# SCH_Motor_PCB_2026-05-03.net
KiCad netlist of a schematic drawn in EasyEDA
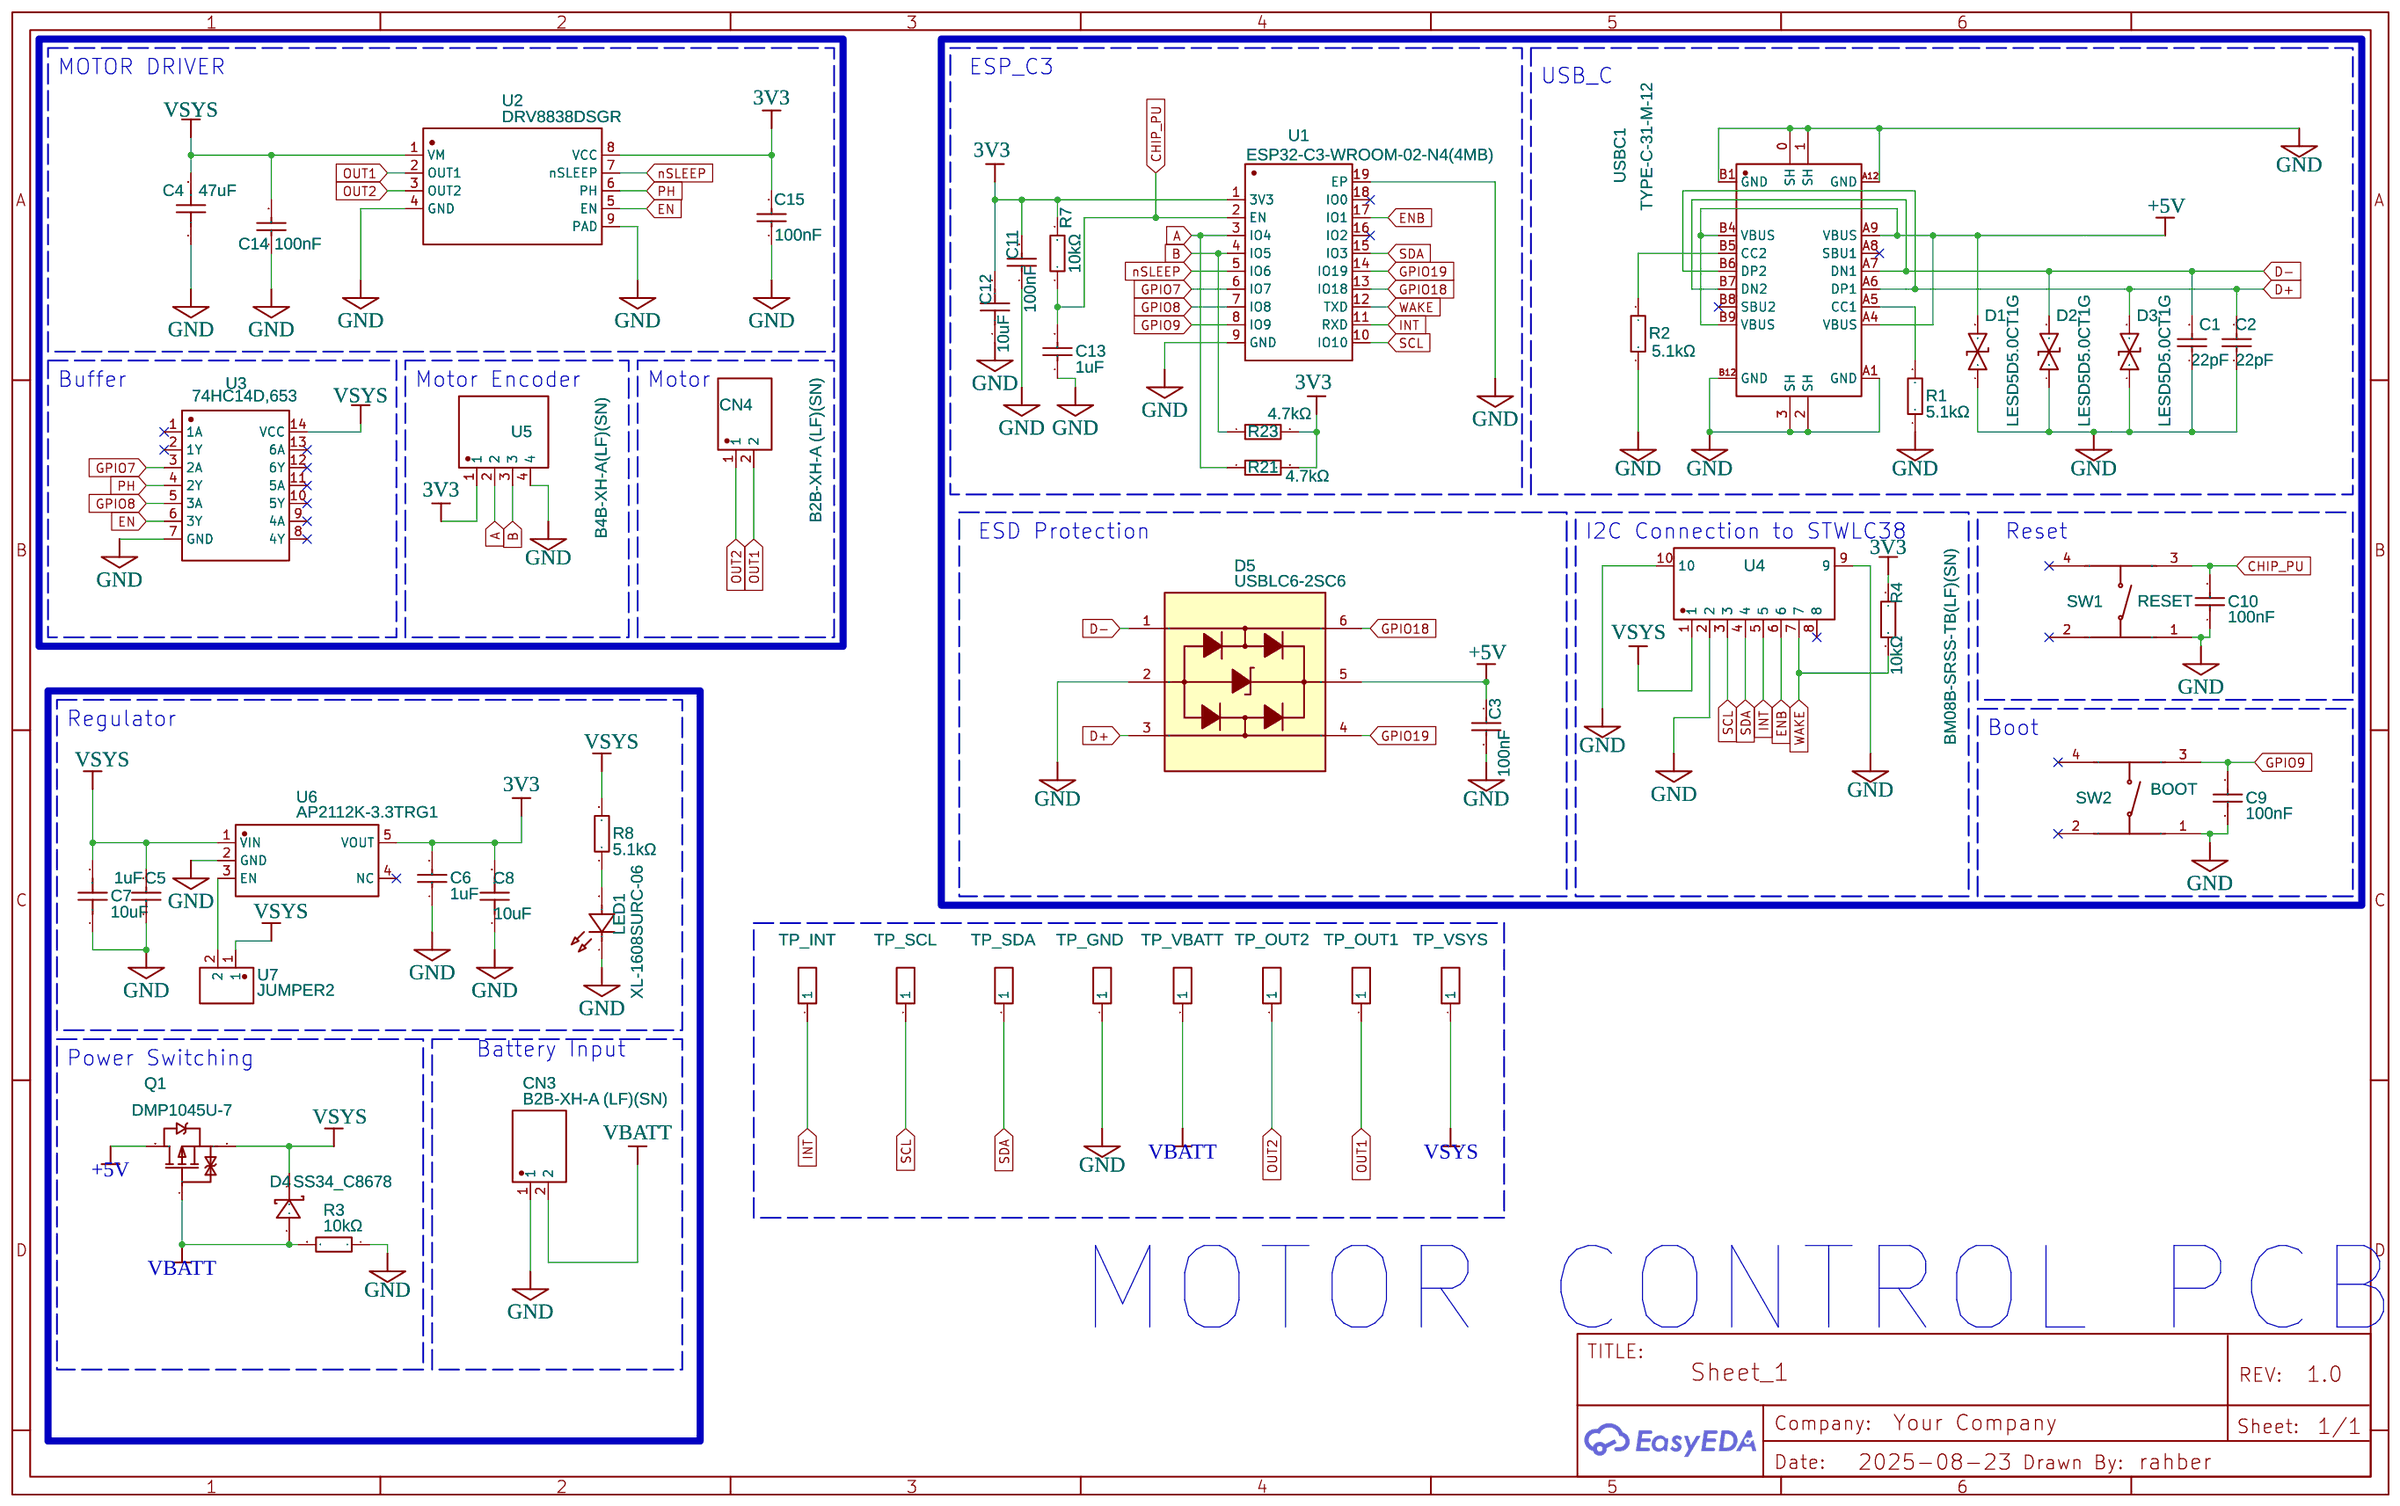
[diagram p0: schematic sheet]

(export (version "E")
  (design (tool "Eeschema 10.0.6"))
  (components
    (comp (ref "BOOT")
      (value "SW2")
      (fields
        (field (name "Manufacturer Part") "TS-1157-C-E")
        (field (name "Manufacturer") "XKB Connectivity(中国星坤)")
      )
      (libsource (lib "") (part "TS-1157-C-E_1"))
    )
    (comp (ref "C1")
      (value "22pF")
      (fields
        (field (name "Manufacturer Part") "CL10C220JB8NNNC")
        (field (name "Manufacturer") "SAMSUNG(三星)")
      )
      (libsource (lib "") (part "CL10C220JB8NNNC"))
    )
    (comp (ref "C2")
      (value "22pF")
      (fields
        (field (name "Manufacturer Part") "CL10C220JB8NNNC")
        (field (name "Manufacturer") "SAMSUNG(三星)")
      )
      (libsource (lib "") (part "CL10C220JB8NNNC"))
    )
    (comp (ref "C3")
      (value "100nF")
      (fields
        (field (name "Manufacturer Part") "CT41G-0603-2X1-50V-0.1μF-K(N)")
        (field (name "Manufacturer") "TORCH(火炬)")
      )
      (libsource (lib "") (part "CT41G-0603-2X1-50V-0.1μF-K(N)"))
    )
    (comp (ref "C4")
      (value "47uF")
      (fields
        (field (name "Manufacturer Part") "CGA0805X5R476M100MT")
        (field (name "Manufacturer") "HRE(芯声)")
      )
      (libsource (lib "") (part "CGA0805X5R476M100MT"))
    )
    (comp (ref "C5")
      (value "1uF")
      (fields
        (field (name "Manufacturer Part") "CL10A105KO8NNNC")
        (field (name "Manufacturer") "SAMSUNG(三星)")
      )
      (libsource (lib "") (part "CL10A105KO8NNNC"))
    )
    (comp (ref "C6")
      (value "1uF")
      (fields
        (field (name "Manufacturer Part") "CL10A105KO8NNNC")
        (field (name "Manufacturer") "SAMSUNG(三星)")
      )
      (libsource (lib "") (part "CL10A105KO8NNNC"))
    )
    (comp (ref "C7")
      (value "10uF")
      (fields
        (field (name "Manufacturer Part") "CL10A106MA8NRNC")
        (field (name "Manufacturer") "SAMSUNG(三星)")
      )
      (libsource (lib "") (part "CL10A106MA8NRNC"))
    )
    (comp (ref "C8")
      (value "10uF")
      (fields
        (field (name "Manufacturer Part") "CL10A106MA8NRNC")
        (field (name "Manufacturer") "SAMSUNG(三星)")
      )
      (libsource (lib "") (part "CL10A106MA8NRNC"))
    )
    (comp (ref "C9")
      (value "100nF")
      (fields
        (field (name "Manufacturer Part") "CT41G-0603-2X1-50V-0.1μF-K(N)")
        (field (name "Manufacturer") "TORCH(火炬)")
      )
      (libsource (lib "") (part "CT41G-0603-2X1-50V-0.1μF-K(N)"))
    )
    (comp (ref "C10")
      (value "100nF")
      (fields
        (field (name "Manufacturer Part") "CT41G-0603-2X1-50V-0.1μF-K(N)")
        (field (name "Manufacturer") "TORCH(火炬)")
      )
      (libsource (lib "") (part "CT41G-0603-2X1-50V-0.1μF-K(N)"))
    )
    (comp (ref "C11")
      (value "100nF")
      (fields
        (field (name "Manufacturer Part") "CT41G-0603-2X1-50V-0.1μF-K(N)")
        (field (name "Manufacturer") "TORCH(火炬)")
      )
      (libsource (lib "") (part "CT41G-0603-2X1-50V-0.1μF-K(N)"))
    )
    (comp (ref "C12")
      (value "10uF")
      (fields
        (field (name "Manufacturer Part") "CL10A106MA8NRNC")
        (field (name "Manufacturer") "SAMSUNG(三星)")
      )
      (libsource (lib "") (part "CL10A106MA8NRNC"))
    )
    (comp (ref "C13")
      (value "1uF")
      (fields
        (field (name "Manufacturer Part") "CL10A105KO8NNNC")
        (field (name "Manufacturer") "SAMSUNG(三星)")
      )
      (libsource (lib "") (part "CL10A105KO8NNNC"))
    )
    (comp (ref "C14")
      (value "100nF")
      (fields
        (field (name "Manufacturer Part") "CT41G-0603-2X1-50V-0.1μF-K(N)")
        (field (name "Manufacturer") "TORCH(火炬)")
      )
      (libsource (lib "") (part "CT41G-0603-2X1-50V-0.1μF-K(N)"))
    )
    (comp (ref "C15")
      (value "100nF")
      (fields
        (field (name "Manufacturer Part") "CT41G-0603-2X1-50V-0.1μF-K(N)")
        (field (name "Manufacturer") "TORCH(火炬)")
      )
      (libsource (lib "") (part "CT41G-0603-2X1-50V-0.1μF-K(N)"))
    )
    (comp (ref "CN3")
      (value "B2B-XH-A (LF)(SN)")
      (fields (field (name "Manufacturer Part") "B2B-XH-A(LF)(SN)") (field (name "Manufacturer") "JST"))
      (libsource (lib "") (part "B2B-XH-A (LF)(SN)"))
    )
    (comp (ref "CN4")
      (value "B2B-XH-A (LF)(SN)")
      (fields (field (name "Manufacturer Part") "B2B-XH-A(LF)(SN)") (field (name "Manufacturer") "JST"))
      (libsource (lib "") (part "B2B-XH-A (LF)(SN)"))
    )
    (comp (ref "D1")
      (value "LESD5D5.0CT1G")
      (fields (field (name "Manufacturer") "LRC(乐山无线电)"))
      (libsource (lib "") (part "LESD5D5.0CT1G"))
    )
    (comp (ref "D2")
      (value "LESD5D5.0CT1G")
      (fields (field (name "Manufacturer") "LRC(乐山无线电)"))
      (libsource (lib "") (part "LESD5D5.0CT1G"))
    )
    (comp (ref "D3")
      (value "LESD5D5.0CT1G")
      (fields (field (name "Manufacturer") "LRC(乐山无线电)"))
      (libsource (lib "") (part "LESD5D5.0CT1G"))
    )
    (comp (ref "D4")
      (value "SS34_C8678")
      (fields (field (name "Manufacturer Part") "SS34") (field (name "Manufacturer") "MDD(辰达半导体)"))
      (libsource (lib "") (part "SS34_C8678"))
    )
    (comp (ref "D5")
      (value "USBLC6-2SC6")
      (fields (field (name "Manufacturer") "ST(意法半导体)"))
      (libsource (lib "") (part "USBLC6-2SC6"))
    )
    (comp (ref "LED1")
      (value "XL-1608SURC-06")
      (fields (field (name "Manufacturer") "XINGLIGHT(成兴光)"))
      (libsource (lib "") (part "XL-1608SURC-06"))
    )
    (comp (ref "Q1")
      (value "DMP1045U-7")
      (fields (field (name "Manufacturer") "DIODES(美台)"))
      (libsource (lib "") (part "DMP1045U-7"))
    )
    (comp (ref "R1")
      (value "5.1kΩ")
      (fields (field (name "Manufacturer Part") "RC0603FR-075K1L") (field (name "Manufacturer") "YAGEO(国巨)"))
      (libsource (lib "") (part "RC0603FR-075K1L"))
    )
    (comp (ref "R2")
      (value "5.1kΩ")
      (fields (field (name "Manufacturer Part") "RC0603FR-075K1L") (field (name "Manufacturer") "YAGEO(国巨)"))
      (libsource (lib "") (part "RC0603FR-075K1L"))
    )
    (comp (ref "R3")
      (value "10kΩ")
      (fields (field (name "Manufacturer Part") "RC0603FR-0710KL") (field (name "Manufacturer") "YAGEO(国巨)"))
      (libsource (lib "") (part "RC0603FR-0710KL"))
    )
    (comp (ref "R4")
      (value "10kΩ")
      (fields (field (name "Manufacturer Part") "RC0603FR-0710KL") (field (name "Manufacturer") "YAGEO(国巨)"))
      (libsource (lib "") (part "RC0603FR-0710KL_2"))
    )
    (comp (ref "R7")
      (value "10kΩ")
      (fields (field (name "Manufacturer Part") "RC0603FR-0710KL") (field (name "Manufacturer") "YAGEO(国巨)"))
      (libsource (lib "") (part "RC0603FR-0710KL_1"))
    )
    (comp (ref "R8")
      (value "5.1kΩ")
      (fields (field (name "Manufacturer Part") "RC0603FR-075K1L") (field (name "Manufacturer") "YAGEO(国巨)"))
      (libsource (lib "") (part "RC0603FR-075K1L"))
    )
    (comp (ref "R21")
      (value "4.7kΩ")
      (fields
        (field (name "Manufacturer Part") "0805W8F4701T5E")
        (field (name "Manufacturer") "UNI-ROYAL(厚声)")
      )
      (libsource (lib "") (part "0805W8F4701T5E"))
    )
    (comp (ref "R23")
      (value "4.7kΩ")
      (fields
        (field (name "Manufacturer Part") "0805W8F4701T5E")
        (field (name "Manufacturer") "UNI-ROYAL(厚声)")
      )
      (libsource (lib "") (part "0805W8F4701T5E"))
    )
    (comp (ref "RESET")
      (value "SW1")
      (fields
        (field (name "Manufacturer Part") "TS-1157-C-E")
        (field (name "Manufacturer") "XKB Connectivity(中国星坤)")
      )
      (libsource (lib "") (part "TS-1157-C-E"))
    )
    (comp (ref "TP_GND") (value "HDR-M-2.54_1x1") (libsource (lib "") (part "HDR-M-2.54_1x1_4")))
    (comp (ref "TP_INT") (value "HDR-M-2.54_1x1") (libsource (lib "") (part "HDR-M-2.54_1x1_5")))
    (comp (ref "TP_OUT1") (value "HDR-M-2.54_1x1") (libsource (lib "") (part "HDR-M-2.54_1x1_3")))
    (comp (ref "TP_OUT2") (value "HDR-M-2.54_1x1") (libsource (lib "") (part "HDR-M-2.54_1x1_3")))
    (comp (ref "TP_SCL") (value "HDR-M-2.54_1x1") (libsource (lib "") (part "HDR-M-2.54_1x1")))
    (comp (ref "TP_SDA") (value "HDR-M-2.54_1x1") (libsource (lib "") (part "HDR-M-2.54_1x1_2")))
    (comp (ref "TP_VBATT") (value "HDR-M-2.54_1x1") (libsource (lib "") (part "HDR-M-2.54_1x1_6")))
    (comp (ref "TP_VSYS") (value "HDR-M-2.54_1x1") (libsource (lib "") (part "HDR-M-2.54_1x1_1")))
    (comp (ref "U1")
      (value "ESP32-C3-WROOM-02-N4(4MB)")
      (fields
        (field (name "Manufacturer Part") "ESP32-C3-WROOM-02-N4")
        (field (name "Manufacturer") "ESPRESSIF(乐鑫)")
      )
      (libsource (lib "") (part "ESP32-C3-WROOM-02-N4(4MB)"))
    )
    (comp (ref "U2")
      (value "DRV8838DSGR")
      (fields (field (name "Manufacturer") "TI(德州仪器)"))
      (libsource (lib "") (part "DRV8838DSGR"))
    )
    (comp (ref "U3")
      (value "74HC14D,653")
      (fields (field (name "Manufacturer") "Nexperia(安世)"))
      (libsource (lib "") (part "74HC14D,653"))
    )
    (comp (ref "U4")
      (value "BM08B-SRSS-TB(LF)(SN)")
      (fields (field (name "Manufacturer") "JST"))
      (libsource (lib "") (part "BM08B-SRSS-TB(LF)(SN)"))
    )
    (comp (ref "U5")
      (value "B4B-XH-A(LF)(SN)")
      (fields (field (name "Manufacturer") "JST"))
      (libsource (lib "") (part "B4B-XH-A(LF)(SN)"))
    )
    (comp (ref "U6")
      (value "AP2112K-3.3TRG1")
      (fields (field (name "Manufacturer") "DIODES(美台)"))
      (libsource (lib "") (part "AP2112K-3.3TRG1"))
    )
    (comp (ref "U7")
      (value "JUMPER2")
      (fields (field (name "Manufacturer Part") "Jumper2"))
      (libsource (lib "") (part "JUMPER2"))
    )
    (comp (ref "USBC1")
      (value "TYPE-C-31-M-12")
      (fields (field (name "Manufacturer") "韩国韩荣"))
      (libsource (lib "") (part "TYPE-C-31-M-12"))
    )
  )
  (nets
    (net (code "1") (name "+5V") (class "Default")
      (node (ref "C3") (pin "2") (pinfunction "2_2") (pintype "input"))
      (node (ref "D1") (pin "2") (pinfunction "2_2") (pintype "unspecified"))
      (node (ref "D5") (pin "5") (pinfunction "5_5") (pintype "input"))
      (node (ref "Q1") (pin "3") (pinfunction "D_3") (pintype "unspecified"))
      (node (ref "USBC1") (pin "A4") (pinfunction "VBUS_A4") (pintype "unspecified"))
      (node (ref "USBC1") (pin "A9") (pinfunction "VBUS_A9") (pintype "unspecified"))
      (node (ref "USBC1") (pin "B4") (pinfunction "VBUS_B4") (pintype "unspecified"))
      (node (ref "USBC1") (pin "B9") (pinfunction "VBUS_B9") (pintype "unspecified"))
    )
    (net (code "2") (name "3V3") (class "Default")
      (node (ref "C11") (pin "2") (pinfunction "2_2") (pintype "input"))
      (node (ref "C12") (pin "2") (pinfunction "2_2") (pintype "unspecified"))
      (node (ref "C15") (pin "2") (pinfunction "2_2") (pintype "input"))
      (node (ref "C6") (pin "2") (pinfunction "2_2") (pintype "input"))
      (node (ref "C8") (pin "2") (pinfunction "2_2") (pintype "unspecified"))
      (node (ref "R21") (pin "2") (pinfunction "2_2") (pintype "input"))
      (node (ref "R23") (pin "2") (pinfunction "2_2") (pintype "input"))
      (node (ref "R4") (pin "1") (pinfunction "1_1") (pintype "input"))
      (node (ref "R7") (pin "2") (pinfunction "2_2") (pintype "input"))
      (node (ref "U1") (pin "1") (pinfunction "3V3_1") (pintype "unspecified"))
      (node (ref "U2") (pin "8") (pinfunction "VCC_8") (pintype "unspecified"))
      (node (ref "U5") (pin "1") (pinfunction "1_1") (pintype "unspecified"))
      (node (ref "U6") (pin "5") (pinfunction "VOUT_5") (pintype "unspecified"))
    )
    (net (code "3") (name "A") (class "Default")
      (node (ref "R21") (pin "1") (pinfunction "1_1") (pintype "input"))
      (node (ref "U1") (pin "3") (pinfunction "IO4_3") (pintype "unspecified"))
      (node (ref "U5") (pin "2") (pinfunction "2_2") (pintype "unspecified"))
    )
    (net (code "4") (name "B") (class "Default")
      (node (ref "R23") (pin "1") (pinfunction "1_1") (pintype "input"))
      (node (ref "U1") (pin "4") (pinfunction "IO5_4") (pintype "unspecified"))
      (node (ref "U5") (pin "3") (pinfunction "3_3") (pintype "unspecified"))
    )
    (net (code "5") (name "CHIP_PU") (class "Default")
      (node (ref "C10") (pin "2") (pinfunction "2_2") (pintype "input"))
      (node (ref "C13") (pin "2") (pinfunction "2_2") (pintype "input"))
      (node (ref "R7") (pin "1") (pinfunction "1_1") (pintype "input"))
      (node (ref "RESET") (pin "3") (pinfunction "C_3") (pintype "unspecified"))
      (node (ref "U1") (pin "2") (pinfunction "EN_2") (pintype "unspecified"))
    )
    (net (code "6") (name "D+") (class "Default")
      (node (ref "C2") (pin "2") (pinfunction "2_2") (pintype "input"))
      (node (ref "D3") (pin "2") (pinfunction "2_2") (pintype "unspecified"))
      (node (ref "D5") (pin "3") (pinfunction "3_3") (pintype "input"))
      (node (ref "USBC1") (pin "A6") (pinfunction "DP1_A6") (pintype "unspecified"))
      (node (ref "USBC1") (pin "B6") (pinfunction "DP2_B6") (pintype "unspecified"))
    )
    (net (code "7") (name "D-") (class "Default")
      (node (ref "C1") (pin "2") (pinfunction "2_2") (pintype "input"))
      (node (ref "D2") (pin "2") (pinfunction "2_2") (pintype "unspecified"))
      (node (ref "D5") (pin "1") (pinfunction "1_1") (pintype "input"))
      (node (ref "USBC1") (pin "A7") (pinfunction "DN1_A7") (pintype "unspecified"))
      (node (ref "USBC1") (pin "B7") (pinfunction "DN2_B7") (pintype "unspecified"))
    )
    (net (code "8") (name "EN") (class "Default")
      (node (ref "U2") (pin "5") (pinfunction "EN_5") (pintype "unspecified"))
      (node (ref "U3") (pin "6") (pinfunction "3Y_6") (pintype "unspecified"))
    )
    (net (code "9") (name "ENB") (class "Default")
      (node (ref "U1") (pin "17") (pinfunction "IO1_17") (pintype "unspecified"))
      (node (ref "U4") (pin "6") (pinfunction "6_6") (pintype "unspecified"))
    )
    (net (code "10") (name "GND") (class "Default")
      (node (ref "BOOT") (pin "1") (pinfunction "A_1") (pintype "unspecified"))
      (node (ref "C1") (pin "1") (pinfunction "1_1") (pintype "input"))
      (node (ref "C10") (pin "1") (pinfunction "1_1") (pintype "input"))
      (node (ref "C11") (pin "1") (pinfunction "1_1") (pintype "input"))
      (node (ref "C12") (pin "1") (pinfunction "1_1") (pintype "unspecified"))
      (node (ref "C13") (pin "1") (pinfunction "1_1") (pintype "input"))
      (node (ref "C14") (pin "1") (pinfunction "1_1") (pintype "input"))
      (node (ref "C15") (pin "1") (pinfunction "1_1") (pintype "input"))
      (node (ref "C2") (pin "1") (pinfunction "1_1") (pintype "input"))
      (node (ref "C3") (pin "1") (pinfunction "1_1") (pintype "input"))
      (node (ref "C4") (pin "1") (pinfunction "1_1") (pintype "unspecified"))
      (node (ref "C5") (pin "1") (pinfunction "1_1") (pintype "input"))
      (node (ref "C6") (pin "1") (pinfunction "1_1") (pintype "input"))
      (node (ref "C7") (pin "1") (pinfunction "1_1") (pintype "unspecified"))
      (node (ref "C8") (pin "1") (pinfunction "1_1") (pintype "unspecified"))
      (node (ref "C9") (pin "1") (pinfunction "1_1") (pintype "input"))
      (node (ref "CN3") (pin "1") (pinfunction "1_1") (pintype "unspecified"))
      (node (ref "D1") (pin "1") (pinfunction "1_1") (pintype "unspecified"))
      (node (ref "D2") (pin "1") (pinfunction "1_1") (pintype "unspecified"))
      (node (ref "D3") (pin "1") (pinfunction "1_1") (pintype "unspecified"))
      (node (ref "D5") (pin "2") (pinfunction "2_2") (pintype "input"))
      (node (ref "LED1") (pin "1") (pinfunction "K_1") (pintype "unspecified"))
      (node (ref "R1") (pin "1") (pinfunction "1_1") (pintype "input"))
      (node (ref "R2") (pin "1") (pinfunction "1_1") (pintype "input"))
      (node (ref "R3") (pin "1") (pinfunction "1_1") (pintype "input"))
      (node (ref "RESET") (pin "1") (pinfunction "A_1") (pintype "unspecified"))
      (node (ref "TP_GND") (pin "1") (pinfunction "1_1") (pintype "input"))
      (node (ref "U1") (pin "19") (pinfunction "EP_19") (pintype "unspecified"))
      (node (ref "U1") (pin "9") (pinfunction "GND_9") (pintype "unspecified"))
      (node (ref "U2") (pin "4") (pinfunction "GND_4") (pintype "unspecified"))
      (node (ref "U2") (pin "9") (pinfunction "PAD_9") (pintype "unspecified"))
      (node (ref "U3") (pin "7") (pinfunction "GND_7") (pintype "unspecified"))
      (node (ref "U4") (pin "10") (pinfunction "10_10") (pintype "unspecified"))
      (node (ref "U4") (pin "2") (pinfunction "2_2") (pintype "unspecified"))
      (node (ref "U4") (pin "9") (pinfunction "9_9") (pintype "unspecified"))
      (node (ref "U5") (pin "4") (pinfunction "4_4") (pintype "unspecified"))
      (node (ref "U6") (pin "2") (pinfunction "GND_2") (pintype "unspecified"))
      (node (ref "USBC1") (pin "0") (pinfunction "SH_0") (pintype "unspecified"))
      (node (ref "USBC1") (pin "1") (pinfunction "SH_1") (pintype "unspecified"))
      (node (ref "USBC1") (pin "2") (pinfunction "SH_2") (pintype "unspecified"))
      (node (ref "USBC1") (pin "3") (pinfunction "SH_3") (pintype "unspecified"))
      (node (ref "USBC1") (pin "A1") (pinfunction "GND_A1") (pintype "unspecified"))
      (node (ref "USBC1") (pin "A12") (pinfunction "GND_A12") (pintype "unspecified"))
      (node (ref "USBC1") (pin "B1") (pinfunction "GND_B1") (pintype "unspecified"))
      (node (ref "USBC1") (pin "B12") (pinfunction "GND_B12") (pintype "unspecified"))
    )
    (net (code "11") (name "GPIO7") (class "Default")
      (node (ref "U1") (pin "6") (pinfunction "IO7_6") (pintype "unspecified"))
      (node (ref "U3") (pin "3") (pinfunction "2A_3") (pintype "unspecified"))
    )
    (net (code "12") (name "GPIO8") (class "Default")
      (node (ref "U1") (pin "7") (pinfunction "IO8_7") (pintype "unspecified"))
      (node (ref "U3") (pin "5") (pinfunction "3A_5") (pintype "unspecified"))
    )
    (net (code "13") (name "GPIO9") (class "Default")
      (node (ref "BOOT") (pin "3") (pinfunction "C_3") (pintype "unspecified"))
      (node (ref "C9") (pin "2") (pinfunction "2_2") (pintype "input"))
      (node (ref "U1") (pin "8") (pinfunction "IO9_8") (pintype "unspecified"))
    )
    (net (code "14") (name "GPIO18") (class "Default")
      (node (ref "D5") (pin "6") (pinfunction "6_6") (pintype "input"))
      (node (ref "U1") (pin "13") (pinfunction "IO18_13") (pintype "unspecified"))
    )
    (net (code "15") (name "GPIO19") (class "Default")
      (node (ref "D5") (pin "4") (pinfunction "4_4") (pintype "input"))
      (node (ref "U1") (pin "14") (pinfunction "IO19_14") (pintype "unspecified"))
    )
    (net (code "16") (name "INT") (class "Default")
      (node (ref "TP_INT") (pin "1") (pinfunction "1_1") (pintype "input"))
      (node (ref "U1") (pin "11") (pinfunction "RXD_11") (pintype "unspecified"))
      (node (ref "U4") (pin "5") (pinfunction "5_5") (pintype "unspecified"))
    )
    (net (code "17") (name "Net-(LED1-A)") (class "Default")
      (node (ref "LED1") (pin "2") (pinfunction "A_2") (pintype "unspecified"))
      (node (ref "R8") (pin "1") (pinfunction "1_1") (pintype "input"))
    )
    (net (code "18") (name "Net-(U6-EN)") (class "Default")
      (node (ref "U6") (pin "3") (pinfunction "EN_3") (pintype "unspecified"))
      (node (ref "U7") (pin "2") (pinfunction "2_2") (pintype "unspecified"))
    )
    (net (code "19") (name "Net-(USBC1-CC1)") (class "Default")
      (node (ref "R1") (pin "2") (pinfunction "2_2") (pintype "input"))
      (node (ref "USBC1") (pin "A5") (pinfunction "CC1_A5") (pintype "unspecified"))
    )
    (net (code "20") (name "Net-(USBC1-CC2)") (class "Default")
      (node (ref "R2") (pin "2") (pinfunction "2_2") (pintype "input"))
      (node (ref "USBC1") (pin "B5") (pinfunction "CC2_B5") (pintype "unspecified"))
    )
    (net (code "21") (name "OUT1") (class "Default")
      (node (ref "CN4") (pin "2") (pinfunction "2_2") (pintype "unspecified"))
      (node (ref "TP_OUT1") (pin "1") (pinfunction "1_1") (pintype "input"))
      (node (ref "U2") (pin "2") (pinfunction "OUT1_2") (pintype "unspecified"))
    )
    (net (code "22") (name "OUT2") (class "Default")
      (node (ref "CN4") (pin "1") (pinfunction "1_1") (pintype "unspecified"))
      (node (ref "TP_OUT2") (pin "1") (pinfunction "1_1") (pintype "input"))
      (node (ref "U2") (pin "3") (pinfunction "OUT2_3") (pintype "unspecified"))
    )
    (net (code "23") (name "PH") (class "Default")
      (node (ref "U2") (pin "6") (pinfunction "PH_6") (pintype "unspecified"))
      (node (ref "U3") (pin "4") (pinfunction "2Y_4") (pintype "unspecified"))
    )
    (net (code "24") (name "SCL") (class "Default")
      (node (ref "TP_SCL") (pin "1") (pinfunction "1_1") (pintype "input"))
      (node (ref "U1") (pin "10") (pinfunction "IO10_10") (pintype "unspecified"))
      (node (ref "U4") (pin "3") (pinfunction "3_3") (pintype "unspecified"))
    )
    (net (code "25") (name "SDA") (class "Default")
      (node (ref "TP_SDA") (pin "1") (pinfunction "1_1") (pintype "input"))
      (node (ref "U1") (pin "15") (pinfunction "IO3_15") (pintype "unspecified"))
      (node (ref "U4") (pin "4") (pinfunction "4_4") (pintype "unspecified"))
    )
    (net (code "26") (name "VBATT") (class "Default")
      (node (ref "CN3") (pin "2") (pinfunction "2_2") (pintype "unspecified"))
      (node (ref "D4") (pin "2") (pinfunction "A_2") (pintype "unspecified"))
      (node (ref "Q1") (pin "1") (pinfunction "G_1") (pintype "unspecified"))
      (node (ref "R3") (pin "2") (pinfunction "2_2") (pintype "input"))
      (node (ref "TP_VBATT") (pin "1") (pinfunction "1_1") (pintype "input"))
    )
    (net (code "27") (name "VSYS") (class "Default")
      (node (ref "C14") (pin "2") (pinfunction "2_2") (pintype "input"))
      (node (ref "C4") (pin "2") (pinfunction "2_2") (pintype "unspecified"))
      (node (ref "C5") (pin "2") (pinfunction "2_2") (pintype "input"))
      (node (ref "C7") (pin "2") (pinfunction "2_2") (pintype "unspecified"))
      (node (ref "D4") (pin "1") (pinfunction "K_1") (pintype "unspecified"))
      (node (ref "Q1") (pin "2") (pinfunction "S_2") (pintype "unspecified"))
      (node (ref "R8") (pin "2") (pinfunction "2_2") (pintype "input"))
      (node (ref "TP_VSYS") (pin "1") (pinfunction "1_1") (pintype "input"))
      (node (ref "U2") (pin "1") (pinfunction "VM_1") (pintype "unspecified"))
      (node (ref "U3") (pin "14") (pinfunction "VCC_14") (pintype "unspecified"))
      (node (ref "U4") (pin "1") (pinfunction "1_1") (pintype "unspecified"))
      (node (ref "U6") (pin "1") (pinfunction "VIN_1") (pintype "unspecified"))
      (node (ref "U7") (pin "1") (pinfunction "1_1") (pintype "unspecified"))
    )
    (net (code "28") (name "WAKE") (class "Default")
      (node (ref "R4") (pin "2") (pinfunction "2_2") (pintype "input"))
      (node (ref "U1") (pin "12") (pinfunction "TXD_12") (pintype "unspecified"))
      (node (ref "U4") (pin "7") (pinfunction "7_7") (pintype "unspecified"))
    )
    (net (code "29") (name "nSLEEP") (class "Default")
      (node (ref "U1") (pin "5") (pinfunction "IO6_5") (pintype "unspecified"))
      (node (ref "U2") (pin "7") (pinfunction "nSLEEP_7") (pintype "unspecified"))
    )
    (net (code "30") (name "unconnected-(BOOT-B-Pad2)") (class "Default")
      (node (ref "BOOT") (pin "2") (pinfunction "B_2") (pintype "unspecified+no_connect"))
    )
    (net (code "31") (name "unconnected-(BOOT-D-Pad4)") (class "Default")
      (node (ref "BOOT") (pin "4") (pinfunction "D_4") (pintype "unspecified+no_connect"))
    )
    (net (code "32") (name "unconnected-(RESET-B-Pad2)") (class "Default")
      (node (ref "RESET") (pin "2") (pinfunction "B_2") (pintype "unspecified+no_connect"))
    )
    (net (code "33") (name "unconnected-(RESET-D-Pad4)") (class "Default")
      (node (ref "RESET") (pin "4") (pinfunction "D_4") (pintype "unspecified+no_connect"))
    )
    (net (code "34") (name "unconnected-(U1-IO0-Pad18)") (class "Default")
      (node (ref "U1") (pin "18") (pinfunction "IO0_18") (pintype "unspecified+no_connect"))
    )
    (net (code "35") (name "unconnected-(U1-IO2-Pad16)") (class "Default")
      (node (ref "U1") (pin "16") (pinfunction "IO2_16") (pintype "unspecified+no_connect"))
    )
    (net (code "36") (name "unconnected-(U3-1A-Pad1)") (class "Default")
      (node (ref "U3") (pin "1") (pinfunction "1A_1") (pintype "unspecified+no_connect"))
    )
    (net (code "37") (name "unconnected-(U3-1Y-Pad2)") (class "Default")
      (node (ref "U3") (pin "2") (pinfunction "1Y_2") (pintype "unspecified+no_connect"))
    )
    (net (code "38") (name "unconnected-(U3-4A-Pad9)") (class "Default")
      (node (ref "U3") (pin "9") (pinfunction "4A_9") (pintype "unspecified+no_connect"))
    )
    (net (code "39") (name "unconnected-(U3-4Y-Pad8)") (class "Default")
      (node (ref "U3") (pin "8") (pinfunction "4Y_8") (pintype "unspecified+no_connect"))
    )
    (net (code "40") (name "unconnected-(U3-5A-Pad11)") (class "Default")
      (node (ref "U3") (pin "11") (pinfunction "5A_11") (pintype "unspecified+no_connect"))
    )
    (net (code "41") (name "unconnected-(U3-5Y-Pad10)") (class "Default")
      (node (ref "U3") (pin "10") (pinfunction "5Y_10") (pintype "unspecified+no_connect"))
    )
    (net (code "42") (name "unconnected-(U3-6A-Pad13)") (class "Default")
      (node (ref "U3") (pin "13") (pinfunction "6A_13") (pintype "unspecified+no_connect"))
    )
    (net (code "43") (name "unconnected-(U3-6Y-Pad12)") (class "Default")
      (node (ref "U3") (pin "12") (pinfunction "6Y_12") (pintype "unspecified+no_connect"))
    )
    (net (code "44") (name "unconnected-(U4-Pad8)") (class "Default")
      (node (ref "U4") (pin "8") (pinfunction "8_8") (pintype "unspecified+no_connect"))
    )
    (net (code "45") (name "unconnected-(U6-NC-Pad4)") (class "Default")
      (node (ref "U6") (pin "4") (pinfunction "NC_4") (pintype "unspecified+no_connect"))
    )
    (net (code "46") (name "unconnected-(USBC1-SBU1-PadA8)") (class "Default")
      (node (ref "USBC1") (pin "A8") (pinfunction "SBU1_A8") (pintype "unspecified+no_connect"))
    )
    (net (code "47") (name "unconnected-(USBC1-SBU2-PadB8)") (class "Default")
      (node (ref "USBC1") (pin "B8") (pinfunction "SBU2_B8") (pintype "unspecified+no_connect"))
    )
  )
)
